# temperatureSensor.net
KiCad netlist of a schematic drawn in EAGLE
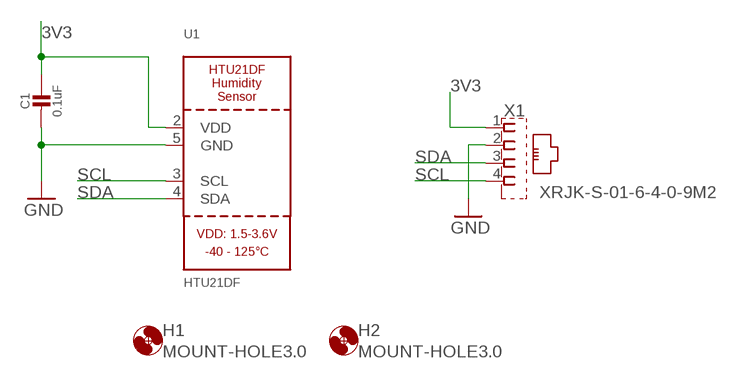
[diagram p0: schematic, sheet 1]

(export (version "E")
  (design (tool "Eeschema 10.0.6"))
  (components
    (comp (ref "C1")
      (value "0.1uF")
      (footprint "eagle-import:0805-NO")
      (libsource (lib "eagle-import") (part "CAP_CERAMIC0805-NOOUTLINE"))
    )
    (comp (ref "H1")
      (value "MOUNT-HOLE3.0")
      (footprint "eagle-import:3,0")
      (libsource (lib "eagle-import") (part "MOUNT-HOLE3.0"))
    )
    (comp (ref "H2")
      (value "MOUNT-HOLE3.0")
      (footprint "eagle-import:3,0")
      (libsource (lib "eagle-import") (part "MOUNT-HOLE3.0"))
    )
    (comp (ref "U1")
      (value "HTU21DF")
      (footprint "eagle-import:HTU21DF")
      (libsource (lib "eagle-import") (part "HTU21DF"))
    )
    (comp (ref "X1")
      (value "XRJK-S-01-6-4-0-9M2")
      (footprint "eagle-import:XRJK-S-01-6-4-0-9M2")
      (libsource (lib "eagle-import") (part "XRJK4-0-9M2-S-01-6-"))
    )
  )
  (nets
    (net (code "1") (name "/3V3") (class "Default")
      (node (ref "C1") (pin "1") (pinfunction "1_1") (pintype "passive"))
      (node (ref "U1") (pin "2") (pinfunction "VDD_2") (pintype "power_in"))
      (node (ref "X1") (pin "1") (pinfunction "1_1") (pintype "passive"))
    )
    (net (code "2") (name "/SCL") (class "Default")
      (node (ref "U1") (pin "3") (pinfunction "SCL_3") (pintype "input"))
      (node (ref "X1") (pin "4") (pinfunction "4_4") (pintype "passive"))
    )
    (net (code "3") (name "/SDA") (class "Default")
      (node (ref "U1") (pin "4") (pinfunction "SDA_4") (pintype "bidirectional"))
      (node (ref "X1") (pin "3") (pinfunction "3_3") (pintype "passive"))
    )
    (net (code "4") (name "GND") (class "Default")
      (node (ref "C1") (pin "2") (pinfunction "2_2") (pintype "passive"))
      (node (ref "U1") (pin "5") (pinfunction "GND_5") (pintype "power_in"))
      (node (ref "X1") (pin "2") (pinfunction "2_2") (pintype "passive"))
    )
  )
)
